# schakelaarDetectie.net
KiCad netlist of a schematic drawn in Altium Designer
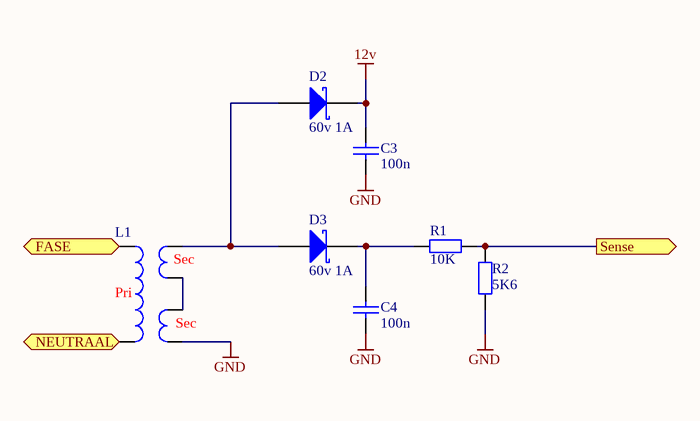
[diagram p0: schakelaarDetectie.SchDoc]

(export (version "E")
  (design (tool "Eeschema 10.0.6"))
  (components
    (comp (ref "C3")
      (value "100n")
      (footprint "C0805")
      (fields
        (field (name "VOLTAGE") "50v")
        (field (name "TOLERANCE") "0.1")
        (field (name "AUTHOR") "Willy Pietersz")
      )
      (libsource (lib "OurDb") (part "cap_NonPolar"))
    )
    (comp (ref "C4")
      (value "100n")
      (footprint "C0805")
      (fields
        (field (name "VOLTAGE") "50v")
        (field (name "TOLERANCE") "0.1")
        (field (name "AUTHOR") "Willy Pietersz")
      )
      (libsource (lib "OurDb") (part "cap_NonPolar"))
    )
    (comp (ref "D2")
      (value "60v 1A")
      (footprint "SOD323")
      (fields
        (field (name "PART NUMBER") "PMEG6010CEJ")
        (field (name "VOLTAGE") "60V")
        (field (name "AUTHOR") "Willem Pietersz")
      )
      (libsource (lib "OurDb") (part "SCHOTTKY"))
    )
    (comp (ref "D3")
      (value "60v 1A")
      (footprint "SOD323")
      (fields
        (field (name "PART NUMBER") "PMEG6010CEJ")
        (field (name "VOLTAGE") "60V")
        (field (name "AUTHOR") "Willem Pietersz")
      )
      (libsource (lib "OurDb") (part "SCHOTTKY"))
    )
    (comp (ref "L1")
      (value "transformer_dual_output")
      (footprint "transformer_Block_1.5VA")
      (description "Inductor")
      (fields (field (name "PART NUMBER") "transformer_220VAC"))
      (libsource (lib "OurDb") (part "transformer_dual_output"))
    )
    (comp (ref "R1")
      (value "10K")
      (footprint "R0805")
      (description "Resistor")
      (fields
        (field (name "POWER") "0.25W")
        (field (name "TOLERANCE") "0.05")
        (field (name "PUBLISHER") "Altium Limited")
        (field (name "AUTHOR") "Willy Pietersz")
      )
      (libsource (lib "") (part "RESISTOR_1"))
    )
    (comp (ref "R2")
      (value "5K6")
      (footprint "R0805")
      (description "Resistor")
      (fields
        (field (name "POWER") "0.25W")
        (field (name "TOLERANCE") "0.05")
        (field (name "PUBLISHER") "Altium Limited")
        (field (name "AUTHOR") "Willy Pietersz")
      )
      (libsource (lib "OurDb") (part "RESISTOR"))
    )
  )
  (nets
    (net (code "1") (name "/FASE") (class "Default")
      (node (ref "L1") (pin "2") (pinfunction "2_2") (pintype "passive"))
    )
    (net (code "2") (name "/NEUTRAAL") (class "Default")
      (node (ref "L1") (pin "1") (pinfunction "1_1") (pintype "passive"))
    )
    (net (code "3") (name "/Sense") (class "Default")
      (node (ref "R1") (pin "2") (pinfunction "2_2") (pintype "passive"))
      (node (ref "R2") (pin "1") (pinfunction "1_1") (pintype "passive"))
    )
    (net (code "4") (name "12v") (class "Default")
      (node (ref "C3") (pin "2") (pinfunction "2_2") (pintype "passive"))
      (node (ref "D2") (pin "2") (pinfunction "2_2") (pintype "passive"))
    )
    (net (code "5") (name "GND") (class "Default")
      (node (ref "C3") (pin "1") (pinfunction "1_1") (pintype "passive"))
      (node (ref "C4") (pin "1") (pinfunction "1_1") (pintype "passive"))
      (node (ref "L1") (pin "3") (pinfunction "1_3") (pintype "passive"))
      (node (ref "R2") (pin "2") (pinfunction "2_2") (pintype "passive"))
    )
    (net (code "6") (name "Net-(C4-Pad2)") (class "Default")
      (node (ref "C4") (pin "2") (pinfunction "2_2") (pintype "passive"))
      (node (ref "D3") (pin "2") (pinfunction "2_2") (pintype "passive"))
      (node (ref "R1") (pin "1") (pinfunction "1_1") (pintype "passive"))
    )
    (net (code "7") (name "Net-(D2-Pad1)") (class "Default")
      (node (ref "D2") (pin "1") (pinfunction "1_1") (pintype "passive"))
      (node (ref "D3") (pin "1") (pinfunction "1_1") (pintype "passive"))
      (node (ref "L1") (pin "6") (pinfunction "2_6") (pintype "passive"))
    )
    (net (code "8") (name "Net-(L1-1-Pad5)") (class "Default")
      (node (ref "L1") (pin "4") (pinfunction "2_4") (pintype "passive"))
      (node (ref "L1") (pin "5") (pinfunction "1_5") (pintype "passive"))
    )
  )
)
